# SolarPanelsAltium.net
KiCad netlist of a schematic drawn in Altium Designer
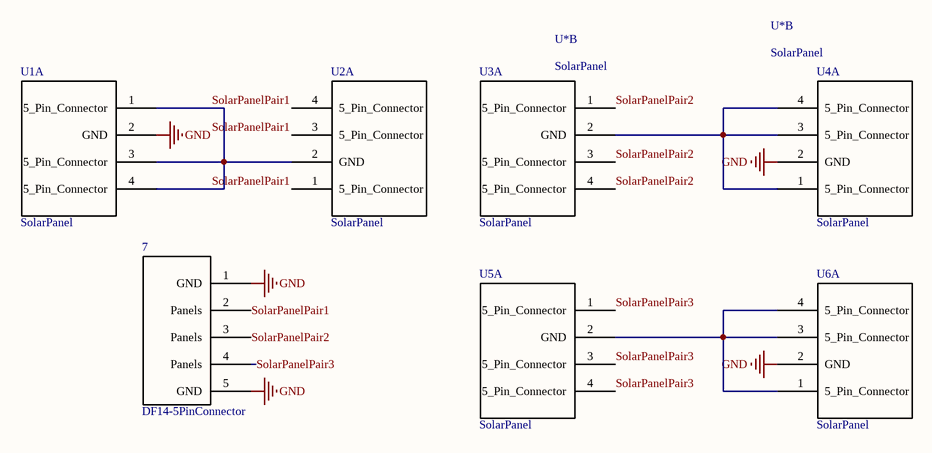
[diagram p0: SolarPanelsAltium.SchDoc]

(export (version "E")
  (design (tool "Eeschema 10.0.6"))
  (components
    (comp (ref "7")
      (value "DF14-5PinConnector")
      (footprint "CONNs:DF14-5P-1.25H(55)")
      (libsource (lib "SolarPanelsSchematicLibrary") (part "DF14-5PinConnector"))
    )
    (comp (ref "U*")
      (value "SolarPanel")
      (footprint "SolarPanel")
      (libsource (lib "SolarPanelsSchematicLibrary") (part "SolarPanel"))
    )
    (comp (ref "U1")
      (value "SolarPanel")
      (footprint "SolarPanel")
      (libsource (lib "SolarPanelsSchematicLibrary") (part "SolarPanel"))
    )
    (comp (ref "U2")
      (value "SolarPanel")
      (footprint "SolarPanel")
      (libsource (lib "SolarPanelsSchematicLibrary") (part "SolarPanel"))
    )
    (comp (ref "U3")
      (value "SolarPanel")
      (footprint "SolarPanel")
      (libsource (lib "SolarPanelsSchematicLibrary") (part "SolarPanel"))
    )
    (comp (ref "U4")
      (value "SolarPanel")
      (footprint "SolarPanel")
      (libsource (lib "SolarPanelsSchematicLibrary") (part "SolarPanel"))
    )
    (comp (ref "U5")
      (value "SolarPanel")
      (footprint "SolarPanel")
      (libsource (lib "SolarPanelsSchematicLibrary") (part "SolarPanel"))
    )
    (comp (ref "U6")
      (value "SolarPanel")
      (footprint "SolarPanel")
      (libsource (lib "SolarPanelsSchematicLibrary") (part "SolarPanel"))
    )
  )
  (nets
    (net (code "1") (name "/SolarPanelPair1") (class "Default")
      (node (ref "7") (pin "2") (pinfunction "Panels_2") (pintype "passive"))
      (node (ref "U2") (pin "1") (pinfunction "5_Pin_Connector_1") (pintype "power_in"))
      (node (ref "U2") (pin "3") (pinfunction "5_Pin_Connector_3") (pintype "power_in"))
      (node (ref "U2") (pin "4") (pinfunction "5_Pin_Connector_4") (pintype "power_in"))
    )
    (net (code "2") (name "/SolarPanelPair2") (class "Default")
      (node (ref "7") (pin "3") (pinfunction "Panels_3") (pintype "passive"))
      (node (ref "U3") (pin "1") (pinfunction "5_Pin_Connector_1") (pintype "power_in"))
      (node (ref "U3") (pin "3") (pinfunction "5_Pin_Connector_3") (pintype "power_in"))
      (node (ref "U3") (pin "4") (pinfunction "5_Pin_Connector_4") (pintype "power_in"))
    )
    (net (code "3") (name "/SolarPanelPair3") (class "Default")
      (node (ref "7") (pin "4") (pinfunction "Panels_4") (pintype "passive"))
      (node (ref "U5") (pin "1") (pinfunction "5_Pin_Connector_1") (pintype "power_in"))
      (node (ref "U5") (pin "3") (pinfunction "5_Pin_Connector_3") (pintype "power_in"))
      (node (ref "U5") (pin "4") (pinfunction "5_Pin_Connector_4") (pintype "power_in"))
    )
    (net (code "4") (name "GND") (class "Default")
      (node (ref "7") (pin "1") (pinfunction "GND_1") (pintype "passive"))
      (node (ref "7") (pin "5") (pinfunction "GND_5") (pintype "passive"))
      (node (ref "U1") (pin "2") (pinfunction "GND_2") (pintype "passive"))
      (node (ref "U4") (pin "2") (pinfunction "GND_2") (pintype "passive"))
      (node (ref "U6") (pin "2") (pinfunction "GND_2") (pintype "passive"))
    )
    (net (code "5") (name "Net-(U2-GND)") (class "Default")
      (node (ref "U1") (pin "1") (pinfunction "5_Pin_Connector_1") (pintype "power_in"))
      (node (ref "U1") (pin "3") (pinfunction "5_Pin_Connector_3") (pintype "power_in"))
      (node (ref "U1") (pin "4") (pinfunction "5_Pin_Connector_4") (pintype "power_in"))
      (node (ref "U2") (pin "2") (pinfunction "GND_2") (pintype "passive"))
    )
    (net (code "6") (name "Net-(U3-GND)") (class "Default")
      (node (ref "U3") (pin "2") (pinfunction "GND_2") (pintype "passive"))
      (node (ref "U4") (pin "1") (pinfunction "5_Pin_Connector_1") (pintype "power_in"))
      (node (ref "U4") (pin "3") (pinfunction "5_Pin_Connector_3") (pintype "power_in"))
      (node (ref "U4") (pin "4") (pinfunction "5_Pin_Connector_4") (pintype "power_in"))
    )
    (net (code "7") (name "Net-(U5-GND)") (class "Default")
      (node (ref "U5") (pin "2") (pinfunction "GND_2") (pintype "passive"))
      (node (ref "U6") (pin "1") (pinfunction "5_Pin_Connector_1") (pintype "power_in"))
      (node (ref "U6") (pin "3") (pinfunction "5_Pin_Connector_3") (pintype "power_in"))
      (node (ref "U6") (pin "4") (pinfunction "5_Pin_Connector_4") (pintype "power_in"))
    )
  )
)
